# peripherals.net
KiCad netlist of a schematic drawn in Altium Designer
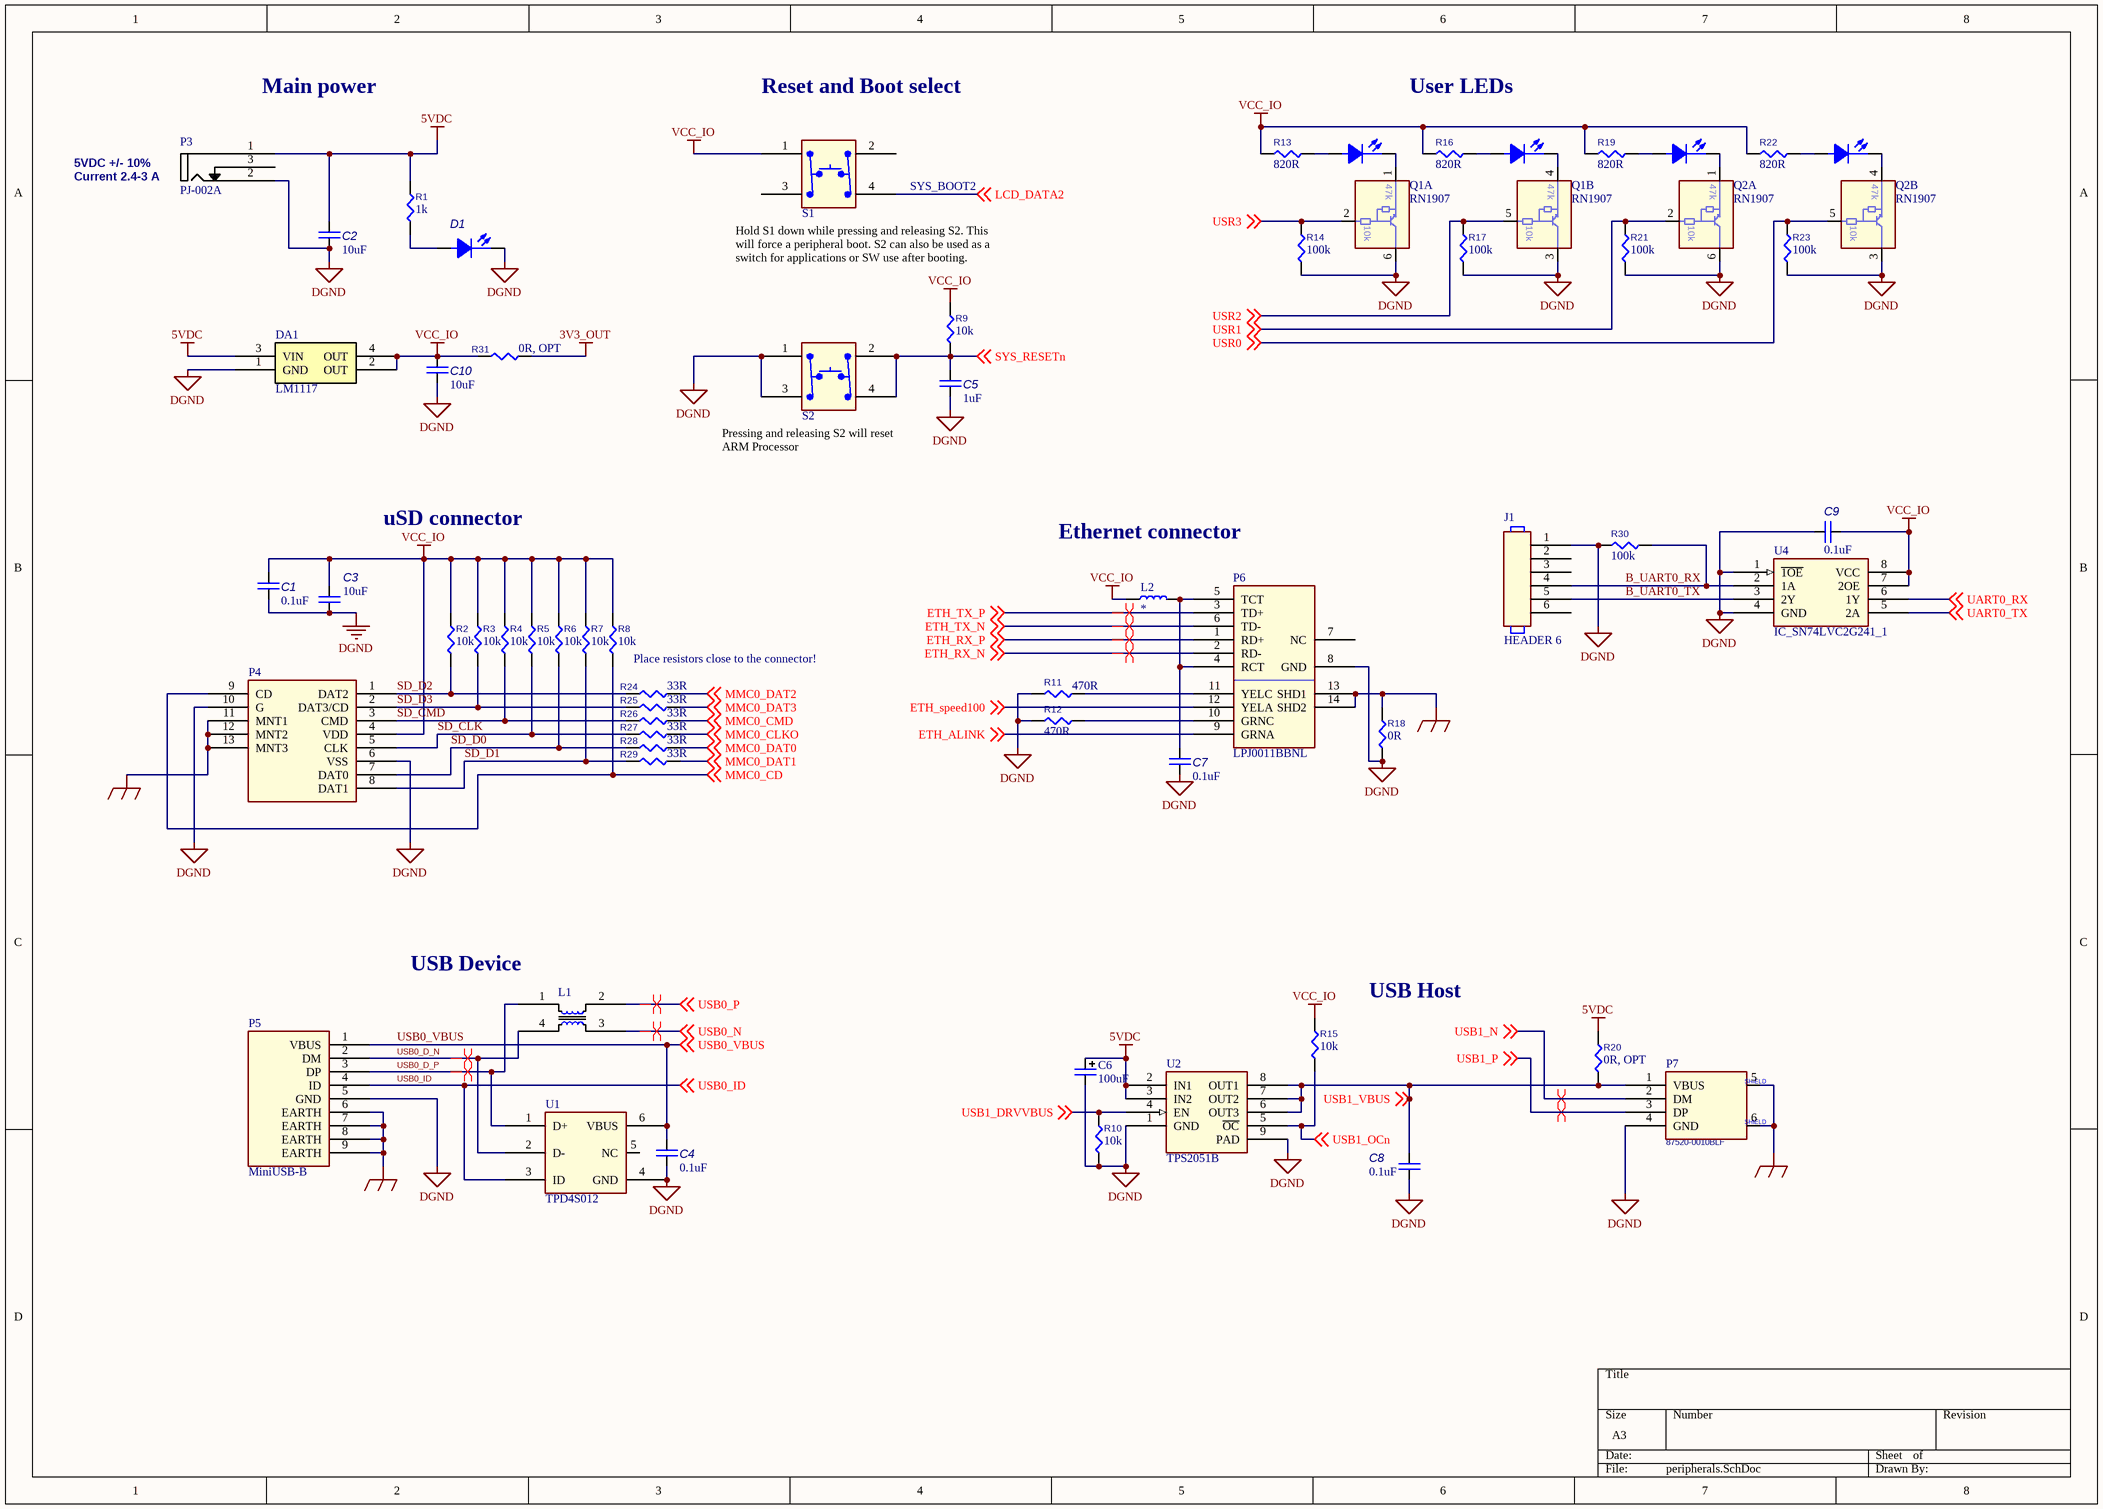
[diagram p0: peripherals.SchDoc]

(export (version "E")
  (design (tool "Eeschema 10.0.6"))
  (components
    (comp (ref "C1")
      (value "0.1uF")
      (footprint "CC1608-0603")
      (description "C0603")
      (libsource (lib "am335x-base") (part "C0603"))
    )
    (comp (ref "C2")
      (value "10uF")
      (footprint "CC2012-0805")
      (description "C0805")
      (libsource (lib "am335x-base") (part "C0805"))
    )
    (comp (ref "C3")
      (value "10uF")
      (footprint "CC2012-0805")
      (description "C0805")
      (libsource (lib "am335x-base") (part "C0805"))
    )
    (comp (ref "C4")
      (value "0.1uF")
      (footprint "CC1608-0603")
      (description "C0603")
      (libsource (lib "am335x-base") (part "C0603"))
    )
    (comp (ref "C5")
      (value "1uF")
      (footprint "CC1608-0603")
      (description "C0603")
      (libsource (lib "am335x-base") (part "C0603"))
    )
    (comp (ref "C6")
      (value "100uF")
      (footprint "Cap_C")
      (description "Tantalum Capacitor Case C")
      (fields (field (name "Comment") "Cap_C"))
      (libsource (lib "am335x-base") (part "Cap_C"))
    )
    (comp (ref "C7")
      (value "0.1uF")
      (footprint "CC1608-0603")
      (description "C0603")
      (libsource (lib "am335x-base") (part "C0603"))
    )
    (comp (ref "C8")
      (value "0.1uF")
      (footprint "CC1608-0603")
      (description "C0603")
      (libsource (lib "am335x-base") (part "C0603"))
    )
    (comp (ref "C9")
      (value "0.1uF")
      (footprint "CC1608-0603")
      (description "C0603")
      (libsource (lib "usomiq-base") (part "C0603"))
    )
    (comp (ref "C10")
      (value "10uF")
      (footprint "CC2012-0805")
      (description "C0805")
      (libsource (lib "am335x-base") (part "C0805"))
    )
    (comp (ref "D1")
      (value "LED0805")
      (footprint "LED0805")
      (description "LED 0805")
      (libsource (lib "am335x-base") (part "LED0805"))
    )
    (comp (ref "D2")
      (value "LED0805")
      (footprint "LED0805")
      (description "LED 0805")
      (libsource (lib "am335x-base") (part "LED0805"))
    )
    (comp (ref "D3")
      (value "LED0805")
      (footprint "LED0805")
      (description "LED 0805")
      (libsource (lib "am335x-base") (part "LED0805"))
    )
    (comp (ref "D4")
      (value "LED0805")
      (footprint "LED0805")
      (description "LED 0805")
      (libsource (lib "am335x-base") (part "LED0805"))
    )
    (comp (ref "D5")
      (value "LED0805")
      (footprint "LED0805")
      (description "LED 0805")
      (libsource (lib "am335x-base") (part "LED0805"))
    )
    (comp (ref "DA1")
      (value "LM1117")
      (footprint "SOT230P700X160-4N")
      (description "800mA Low-Dropout Linear Regulator")
      (fields (field (name "MANUFACTURER") "National"))
      (libsource (lib "usomiq-base") (part "LM1117"))
    )
    (comp (ref "J1")
      (value "HEADER 6")
      (footprint "DIP6")
      (description "CONN HEADER 6POS, VERTICAL,  .100 STR TIN")
      (fields (field (name "MFR") "FCI"))
      (libsource (lib "usomiq-base") (part "HEADER 6"))
    )
    (comp (ref "L1")
      (value "DLW21H")
      (footprint "DLW21H")
      (description "Low profile wire-wound common choke coil")
      (fields (field (name "MANUFACTURER") "Murata"))
      (libsource (lib "am335x-base") (part "DLW21H"))
    )
    (comp (ref "L2")
      (value "BLM18A-FB")
      (footprint "CHIP0603")
      (description "Chip EMIFILr Inductor Type")
      (fields (field (name "MANUFACTURER") "Murata") (field (name "MAN P/N") "*"))
      (libsource (lib "am335x-base") (part "BLM18A-FB"))
    )
    (comp (ref "P3")
      (value "PJ-002A")
      (footprint "PJ-002A")
      (description "DC POWER JACK")
      (fields (field (name "MANUFACTURER") "CIU Inc"))
      (libsource (lib "omap") (part "PJ-002A"))
    )
    (comp (ref "P4")
      (value "~")
      (footprint "TFC08WP01F-A-R1K-H")
      (description "Connector for microSD™ Card (Push-push Type)")
      (fields (field (name "MFR") "AUK Contractors Co, LTD"))
      (libsource (lib "usomiq-base") (part "TFC08WP01F-R1K-H-CN"))
    )
    (comp (ref "P5")
      (value "MiniUSB-B")
      (footprint "MINI-USB-B5 SMT")
      (description "Mini USB Type B CONNECTOR")
      (fields (field (name "MFR") "Hirose"))
      (libsource (lib "usomiq-base") (part "MiniUSB-B"))
    )
    (comp (ref "P6")
      (value "CONN_RJ45_MAG_WE_0")
      (footprint "TRJ0011ABNL")
      (description "RJ-45 10/100 W/Magnetics")
      (fields (field (name "MFR") "Link PP") (field (name "P/N") "LPJ0011BBNL"))
      (libsource (lib "am335x-base") (part "CONN_RJ45_MAG_WE_0"))
    )
    (comp (ref "P7")
      (value "CONN_54819-0578_2")
      (footprint "USB2.5-2H4C")
      (description "USB Type A Connectors")
      (fields (field (name "P/N") "87520-0010BLF") (field (name "MFR") "FCI"))
      (libsource (lib "am335x-base") (part "CONN_54819-0578_2"))
    )
    (comp (ref "Q1")
      (value "RN1907")
      (footprint "SOT363-6L")
      (description "Transistor Silicon NPN")
      (fields (field (name "MFR") "Panasonic"))
      (libsource (lib "am335x-base") (part "RN1907"))
    )
    (comp (ref "Q2")
      (value "RN1907")
      (footprint "SOT363-6L")
      (description "Transistor Silicon NPN")
      (fields (field (name "MFR") "Panasonic"))
      (libsource (lib "am335x-base") (part "RN1907"))
    )
    (comp (ref "R1")
      (value "1k")
      (footprint "RESC1608X55N")
      (description "R0603")
      (libsource (lib "am335x-base") (part "R0603"))
    )
    (comp (ref "R2")
      (value "10k")
      (footprint "RESC1608X55N")
      (description "R0603")
      (libsource (lib "am335x-base") (part "R0603"))
    )
    (comp (ref "R3")
      (value "10k")
      (footprint "RESC1608X55N")
      (description "R0603")
      (libsource (lib "am335x-base") (part "R0603"))
    )
    (comp (ref "R4")
      (value "10k")
      (footprint "RESC1608X55N")
      (description "R0603")
      (libsource (lib "am335x-base") (part "R0603"))
    )
    (comp (ref "R5")
      (value "10k")
      (footprint "RESC1608X55N")
      (description "R0603")
      (libsource (lib "am335x-base") (part "R0603"))
    )
    (comp (ref "R6")
      (value "10k")
      (footprint "RESC1608X55N")
      (description "R0603")
      (libsource (lib "am335x-base") (part "R0603"))
    )
    (comp (ref "R7")
      (value "10k")
      (footprint "RESC1608X55N")
      (description "R0603")
      (libsource (lib "am335x-base") (part "R0603"))
    )
    (comp (ref "R8")
      (value "10k")
      (footprint "RESC1608X55N")
      (description "R0603")
      (libsource (lib "am335x-base") (part "R0603"))
    )
    (comp (ref "R9")
      (value "10k")
      (footprint "RESC1608X55N")
      (description "R0603")
      (libsource (lib "am335x-base") (part "R0603"))
    )
    (comp (ref "R10")
      (value "10k")
      (footprint "RESC1608X55N")
      (description "R0603")
      (libsource (lib "am335x-base") (part "R0603"))
    )
    (comp (ref "R11")
      (value "470R")
      (footprint "RESC1608X55N")
      (description "R0603")
      (libsource (lib "am335x-base") (part "R0603"))
    )
    (comp (ref "R12")
      (value "470R")
      (footprint "RESC1608X55N")
      (description "R0603")
      (libsource (lib "am335x-base") (part "R0603"))
    )
    (comp (ref "R13")
      (value "820R")
      (footprint "RESC1608X55N")
      (description "R0603")
      (libsource (lib "am335x-base") (part "R0603"))
    )
    (comp (ref "R14")
      (value "100k")
      (footprint "RESC1608X55N")
      (description "R0603")
      (libsource (lib "am335x-base") (part "R0603"))
    )
    (comp (ref "R15")
      (value "10k")
      (footprint "RESC1608X55N")
      (description "R0603")
      (libsource (lib "am335x-base") (part "R0603"))
    )
    (comp (ref "R16")
      (value "820R")
      (footprint "RESC1608X55N")
      (description "R0603")
      (libsource (lib "am335x-base") (part "R0603"))
    )
    (comp (ref "R17")
      (value "100k")
      (footprint "RESC1608X55N")
      (description "R0603")
      (libsource (lib "am335x-base") (part "R0603"))
    )
    (comp (ref "R18")
      (value "0R")
      (footprint "RESC1608X55N")
      (description "R0603")
      (libsource (lib "am335x-base") (part "R0603"))
    )
    (comp (ref "R19")
      (value "820R")
      (footprint "RESC1608X55N")
      (description "R0603")
      (libsource (lib "am335x-base") (part "R0603"))
    )
    (comp (ref "R20")
      (value "0R, OPT")
      (footprint "RESC1608X55N")
      (description "R0603")
      (libsource (lib "am335x-base") (part "R0603"))
    )
    (comp (ref "R21")
      (value "100k")
      (footprint "RESC1608X55N")
      (description "R0603")
      (libsource (lib "am335x-base") (part "R0603"))
    )
    (comp (ref "R22")
      (value "820R")
      (footprint "RESC1608X55N")
      (description "R0603")
      (libsource (lib "am335x-base") (part "R0603"))
    )
    (comp (ref "R23")
      (value "100k")
      (footprint "RESC1608X55N")
      (description "R0603")
      (libsource (lib "am335x-base") (part "R0603"))
    )
    (comp (ref "R24")
      (value "33R")
      (footprint "RESC1608X55N")
      (description "R0603")
      (libsource (lib "usomiq-base") (part "R0603"))
    )
    (comp (ref "R25")
      (value "33R")
      (footprint "RESC1608X55N")
      (description "R0603")
      (libsource (lib "usomiq-base") (part "R0603"))
    )
    (comp (ref "R26")
      (value "33R")
      (footprint "RESC1608X55N")
      (description "R0603")
      (libsource (lib "usomiq-base") (part "R0603"))
    )
    (comp (ref "R27")
      (value "33R")
      (footprint "RESC1608X55N")
      (description "R0603")
      (libsource (lib "usomiq-base") (part "R0603"))
    )
    (comp (ref "R28")
      (value "33R")
      (footprint "RESC1608X55N")
      (description "R0603")
      (libsource (lib "usomiq-base") (part "R0603"))
    )
    (comp (ref "R29")
      (value "33R")
      (footprint "RESC1608X55N")
      (description "R0603")
      (libsource (lib "usomiq-base") (part "R0603"))
    )
    (comp (ref "R30")
      (value "100k")
      (footprint "RESC1608X55N")
      (description "R0603")
      (libsource (lib "am335x-base") (part "R0603"))
    )
    (comp (ref "R31")
      (value "0R, OPT")
      (footprint "RESC1608X55N")
      (description "R0603")
      (libsource (lib "usomiq-base") (part "R0603"))
    )
    (comp (ref "S1")
      (value "SW_KT11P2JM_2")
      (footprint "KMR231GLFS")
      (description "SMD button")
      (fields (field (name "MFR") "C&K Components"))
      (libsource (lib "usomiq-base") (part "SW_KT11P2JM_2"))
    )
    (comp (ref "S2")
      (value "SW_KT11P2JM_2")
      (footprint "KMR231GLFS")
      (description "SMD button")
      (fields (field (name "MFR") "C&K Components"))
      (libsource (lib "usomiq-base") (part "SW_KT11P2JM_2"))
    )
    (comp (ref "U1")
      (value "TPD4S012")
      (footprint "s-puson-n6")
      (description "4-Channel USB ESD Solution with Power Clamp")
      (fields (field (name "MFR") "TI"))
      (libsource (lib "usomiq-base") (part "TPD4S012"))
    )
    (comp (ref "U2")
      (value "TPS2051B")
      (footprint "R-PDSO-G8")
      (description "CURRENT-LIMITED, POWER-DISTRIBUTION SWITCHES")
      (fields (field (name "MFR") "TI"))
      (libsource (lib "usomiq-base") (part "TPS2051B"))
    )
    (comp (ref "U4")
      (value "IC_SN74LVC2G241_1")
      (footprint "SOP127P600-8N")
      (description "Dual Buffer/Driver With 3-State Outputs")
      (fields (field (name "MFR") "TI"))
      (libsource (lib "usomiq-base") (part "IC_SN74LVC2G241_1"))
    )
  )
  (nets
    (net (code "1") (name "/B_UART0_RX") (class "Default")
      (node (ref "J1") (pin "4") (pinfunction "4_4") (pintype "passive"))
      (node (ref "R30") (pin "1") (pinfunction "1_1") (pintype "passive"))
      (node (ref "U4") (pin "2") (pinfunction "1A_2") (pintype "passive"))
    )
    (net (code "2") (name "/B_UART0_TX") (class "Default")
      (node (ref "J1") (pin "5") (pinfunction "5_5") (pintype "passive"))
      (node (ref "U4") (pin "3") (pinfunction "2Y_3") (pintype "passive"))
    )
    (net (code "3") (name "/SD_CLK") (class "Default")
      (node (ref "P4") (pin "5") (pinfunction "CLK_5") (pintype "passive"))
      (node (ref "R27") (pin "1") (pinfunction "1_1") (pintype "passive"))
      (node (ref "R5") (pin "1") (pinfunction "1_1") (pintype "passive"))
    )
    (net (code "4") (name "/SD_CMD") (class "Default")
      (node (ref "P4") (pin "3") (pinfunction "CMD_3") (pintype "passive"))
      (node (ref "R26") (pin "1") (pinfunction "1_1") (pintype "passive"))
      (node (ref "R4") (pin "1") (pinfunction "1_1") (pintype "passive"))
    )
    (net (code "5") (name "/SD_D0") (class "Default")
      (node (ref "P4") (pin "7") (pinfunction "DAT0_7") (pintype "passive"))
      (node (ref "R28") (pin "1") (pinfunction "1_1") (pintype "passive"))
      (node (ref "R6") (pin "1") (pinfunction "1_1") (pintype "passive"))
    )
    (net (code "6") (name "/SD_D1") (class "Default")
      (node (ref "P4") (pin "8") (pinfunction "DAT1_8") (pintype "passive"))
      (node (ref "R29") (pin "1") (pinfunction "1_1") (pintype "passive"))
      (node (ref "R7") (pin "1") (pinfunction "1_1") (pintype "passive"))
    )
    (net (code "7") (name "/SD_D2") (class "Default")
      (node (ref "P4") (pin "1") (pinfunction "DAT2_1") (pintype "passive"))
      (node (ref "R2") (pin "1") (pinfunction "1_1") (pintype "passive"))
      (node (ref "R24") (pin "1") (pinfunction "1_1") (pintype "passive"))
    )
    (net (code "8") (name "/SD_D3") (class "Default")
      (node (ref "P4") (pin "2") (pinfunction "DAT3/CD_2") (pintype "passive"))
      (node (ref "R25") (pin "1") (pinfunction "1_1") (pintype "passive"))
      (node (ref "R3") (pin "1") (pinfunction "1_1") (pintype "passive"))
    )
    (net (code "9") (name "/USB0_D_N") (class "Default")
      (node (ref "L1") (pin "4") (pinfunction "4_4") (pintype "passive"))
      (node (ref "P5") (pin "2") (pinfunction "DM_2") (pintype "passive"))
      (node (ref "U1") (pin "2") (pinfunction "D-_2") (pintype "passive"))
    )
    (net (code "10") (name "/USB0_D_P") (class "Default")
      (node (ref "L1") (pin "1") (pinfunction "1_1") (pintype "passive"))
      (node (ref "P5") (pin "3") (pinfunction "DP_3") (pintype "passive"))
      (node (ref "U1") (pin "1") (pinfunction "D+_1") (pintype "passive"))
    )
    (net (code "11") (name "3V3_OUT") (class "Default")
      (node (ref "R31") (pin "2") (pinfunction "2_2") (pintype "passive"))
    )
    (net (code "12") (name "5VDC") (class "Default")
      (node (ref "C2") (pin "2") (pinfunction "2_2") (pintype "passive"))
      (node (ref "C6") (pin "1") (pinfunction "1_1") (pintype "passive"))
      (node (ref "DA1") (pin "3") (pinfunction "VIN_3") (pintype "power_in"))
      (node (ref "P3") (pin "1") (pinfunction "GND_1") (pintype "passive"))
      (node (ref "R1") (pin "2") (pinfunction "2_2") (pintype "passive"))
      (node (ref "R20") (pin "2") (pinfunction "2_2") (pintype "passive"))
      (node (ref "U2") (pin "2") (pinfunction "IN1_2") (pintype "power_in"))
      (node (ref "U2") (pin "3") (pinfunction "IN2_3") (pintype "power_in"))
    )
    (net (code "13") (name "DGND") (class "Default")
      (node (ref "C1") (pin "2") (pinfunction "2_2") (pintype "passive"))
      (node (ref "C10") (pin "1") (pinfunction "1_1") (pintype "passive"))
      (node (ref "C2") (pin "1") (pinfunction "1_1") (pintype "passive"))
      (node (ref "C3") (pin "1") (pinfunction "1_1") (pintype "passive"))
      (node (ref "C4") (pin "2") (pinfunction "2_2") (pintype "passive"))
      (node (ref "C5") (pin "2") (pinfunction "2_2") (pintype "passive"))
      (node (ref "C6") (pin "2") (pinfunction "2_2") (pintype "passive"))
      (node (ref "C7") (pin "2") (pinfunction "2_2") (pintype "passive"))
      (node (ref "C8") (pin "1") (pinfunction "1_1") (pintype "passive"))
      (node (ref "C9") (pin "1") (pinfunction "1_1") (pintype "passive"))
      (node (ref "D1") (pin "2") (pinfunction "C_2") (pintype "passive"))
      (node (ref "DA1") (pin "1") (pinfunction "GND_1") (pintype "power_in"))
      (node (ref "J1") (pin "1") (pinfunction "1_1") (pintype "passive"))
      (node (ref "P3") (pin "2") (pinfunction "RIGHT_2") (pintype "passive"))
      (node (ref "P4") (pin "10") (pinfunction "G_10") (pintype "passive"))
      (node (ref "P4") (pin "6") (pinfunction "VSS_6") (pintype "power_in"))
      (node (ref "P5") (pin "5") (pinfunction "GND_5") (pintype "power_in"))
      (node (ref "P6") (pin "8") (pinfunction "GND_8") (pintype "passive"))
      (node (ref "P7") (pin "4") (pinfunction "GND_4") (pintype "passive"))
      (node (ref "Q1") (pin "3") (pinfunction "3_3") (pintype "passive"))
      (node (ref "Q1") (pin "6") (pinfunction "3_6") (pintype "passive"))
      (node (ref "Q2") (pin "3") (pinfunction "3_3") (pintype "passive"))
      (node (ref "Q2") (pin "6") (pinfunction "3_6") (pintype "passive"))
      (node (ref "R10") (pin "1") (pinfunction "1_1") (pintype "passive"))
      (node (ref "R11") (pin "1") (pinfunction "1_1") (pintype "passive"))
      (node (ref "R12") (pin "1") (pinfunction "1_1") (pintype "passive"))
      (node (ref "R14") (pin "1") (pinfunction "1_1") (pintype "passive"))
      (node (ref "R17") (pin "1") (pinfunction "1_1") (pintype "passive"))
      (node (ref "R18") (pin "1") (pinfunction "1_1") (pintype "passive"))
      (node (ref "R21") (pin "1") (pinfunction "1_1") (pintype "passive"))
      (node (ref "R23") (pin "1") (pinfunction "1_1") (pintype "passive"))
      (node (ref "R30") (pin "2") (pinfunction "2_2") (pintype "passive"))
      (node (ref "S2") (pin "1") (pinfunction "A1_1") (pintype "passive"))
      (node (ref "S2") (pin "3") (pinfunction "A2_3") (pintype "passive"))
      (node (ref "U1") (pin "4") (pinfunction "GND_4") (pintype "power_in"))
      (node (ref "U2") (pin "1") (pinfunction "GND_1") (pintype "power_in"))
      (node (ref "U2") (pin "9") (pinfunction "PAD_9") (pintype "passive"))
      (node (ref "U4") (pin "1") (pinfunction "~{1OE}_1") (pintype "input"))
      (node (ref "U4") (pin "4") (pinfunction "GND_4") (pintype "power_in"))
    )
    (net (code "14") (name "EARTH") (class "Default")
      (node (ref "P4") (pin "11") (pinfunction "MNT1_11") (pintype "passive"))
      (node (ref "P4") (pin "12") (pinfunction "MNT2_12") (pintype "passive"))
      (node (ref "P4") (pin "13") (pinfunction "MNT3_13") (pintype "passive"))
      (node (ref "P5") (pin "6") (pinfunction "EARTH_6") (pintype "passive"))
      (node (ref "P5") (pin "7") (pinfunction "EARTH_7") (pintype "passive"))
      (node (ref "P5") (pin "8") (pinfunction "EARTH_8") (pintype "passive"))
      (node (ref "P5") (pin "9") (pinfunction "EARTH_9") (pintype "passive"))
      (node (ref "P6") (pin "13") (pinfunction "SHD1_13") (pintype "passive"))
      (node (ref "P6") (pin "14") (pinfunction "SHD2_14") (pintype "passive"))
      (node (ref "P7") (pin "5") (pinfunction "SHELD1_5") (pintype "passive"))
      (node (ref "P7") (pin "6") (pinfunction "PAD4_6") (pintype "passive"))
      (node (ref "R18") (pin "2") (pinfunction "2_2") (pintype "passive"))
    )
    (net (code "15") (name "ETH_ALINK") (class "Default")
      (node (ref "P6") (pin "9") (pinfunction "GRNA_9") (pintype "passive"))
    )
    (net (code "16") (name "ETH_RX_N") (class "Default")
      (node (ref "P6") (pin "2") (pinfunction "RD-_2") (pintype "passive"))
    )
    (net (code "17") (name "ETH_RX_P") (class "Default")
      (node (ref "P6") (pin "1") (pinfunction "RD+_1") (pintype "passive"))
    )
    (net (code "18") (name "ETH_TX_N") (class "Default")
      (node (ref "P6") (pin "6") (pinfunction "TD-_6") (pintype "passive"))
    )
    (net (code "19") (name "ETH_TX_P") (class "Default")
      (node (ref "P6") (pin "3") (pinfunction "TD+_3") (pintype "passive"))
    )
    (net (code "20") (name "ETH_speed100") (class "Default")
      (node (ref "P6") (pin "12") (pinfunction "YELA_12") (pintype "passive"))
    )
    (net (code "21") (name "LCD_DATA2") (class "Default")
      (node (ref "S1") (pin "4") (pinfunction "B2_4") (pintype "passive"))
    )
    (net (code "22") (name "MMC0_CD") (class "Default")
      (node (ref "P4") (pin "9") (pinfunction "CD_9") (pintype "passive"))
      (node (ref "R8") (pin "1") (pinfunction "1_1") (pintype "passive"))
    )
    (net (code "23") (name "MMC0_CLKO") (class "Default")
      (node (ref "R27") (pin "2") (pinfunction "2_2") (pintype "passive"))
    )
    (net (code "24") (name "MMC0_CMD") (class "Default")
      (node (ref "R26") (pin "2") (pinfunction "2_2") (pintype "passive"))
    )
    (net (code "25") (name "MMC0_DAT0") (class "Default")
      (node (ref "R28") (pin "2") (pinfunction "2_2") (pintype "passive"))
    )
    (net (code "26") (name "MMC0_DAT1") (class "Default")
      (node (ref "R29") (pin "2") (pinfunction "2_2") (pintype "passive"))
    )
    (net (code "27") (name "MMC0_DAT2") (class "Default")
      (node (ref "R24") (pin "2") (pinfunction "2_2") (pintype "passive"))
    )
    (net (code "28") (name "MMC0_DAT3") (class "Default")
      (node (ref "R25") (pin "2") (pinfunction "2_2") (pintype "passive"))
    )
    (net (code "29") (name "Net-(D1-A)") (class "Default")
      (node (ref "D1") (pin "1") (pinfunction "A_1") (pintype "passive"))
      (node (ref "R1") (pin "1") (pinfunction "1_1") (pintype "passive"))
    )
    (net (code "30") (name "Net-(D2-A)") (class "Default")
      (node (ref "D2") (pin "1") (pinfunction "A_1") (pintype "passive"))
      (node (ref "R13") (pin "1") (pinfunction "1_1") (pintype "passive"))
    )
    (net (code "31") (name "Net-(D2-C)") (class "Default")
      (node (ref "D2") (pin "2") (pinfunction "C_2") (pintype "passive"))
      (node (ref "Q1") (pin "1") (pinfunction "4_1") (pintype "passive"))
    )
    (net (code "32") (name "Net-(D3-A)") (class "Default")
      (node (ref "D3") (pin "1") (pinfunction "A_1") (pintype "passive"))
      (node (ref "R16") (pin "1") (pinfunction "1_1") (pintype "passive"))
    )
    (net (code "33") (name "Net-(D3-C)") (class "Default")
      (node (ref "D3") (pin "2") (pinfunction "C_2") (pintype "passive"))
      (node (ref "Q1") (pin "4") (pinfunction "4_4") (pintype "passive"))
    )
    (net (code "34") (name "Net-(D4-A)") (class "Default")
      (node (ref "D4") (pin "1") (pinfunction "A_1") (pintype "passive"))
      (node (ref "R19") (pin "1") (pinfunction "1_1") (pintype "passive"))
    )
    (net (code "35") (name "Net-(D4-C)") (class "Default")
      (node (ref "D4") (pin "2") (pinfunction "C_2") (pintype "passive"))
      (node (ref "Q2") (pin "1") (pinfunction "4_1") (pintype "passive"))
    )
    (net (code "36") (name "Net-(D5-A)") (class "Default")
      (node (ref "D5") (pin "1") (pinfunction "A_1") (pintype "passive"))
      (node (ref "R22") (pin "1") (pinfunction "1_1") (pintype "passive"))
    )
    (net (code "37") (name "Net-(D5-C)") (class "Default")
      (node (ref "D5") (pin "2") (pinfunction "C_2") (pintype "passive"))
      (node (ref "Q2") (pin "4") (pinfunction "4_4") (pintype "passive"))
    )
    (net (code "38") (name "Net-(P6-GRNC)") (class "Default")
      (node (ref "P6") (pin "10") (pinfunction "GRNC_10") (pintype "passive"))
      (node (ref "R12") (pin "2") (pinfunction "2_2") (pintype "passive"))
    )
    (net (code "39") (name "Net-(P6-RCT)") (class "Default")
      (node (ref "C7") (pin "1") (pinfunction "1_1") (pintype "passive"))
      (node (ref "L2") (pin "2") (pinfunction "2_2") (pintype "passive"))
      (node (ref "P6") (pin "4") (pinfunction "RCT_4") (pintype "passive"))
      (node (ref "P6") (pin "5") (pinfunction "TCT_5") (pintype "passive"))
    )
    (net (code "40") (name "Net-(P6-YELC)") (class "Default")
      (node (ref "P6") (pin "11") (pinfunction "YELC_11") (pintype "passive"))
      (node (ref "R11") (pin "2") (pinfunction "2_2") (pintype "passive"))
    )
    (net (code "41") (name "SYS_RESETn") (class "Default")
      (node (ref "C5") (pin "1") (pinfunction "1_1") (pintype "passive"))
      (node (ref "R9") (pin "1") (pinfunction "1_1") (pintype "passive"))
      (node (ref "S2") (pin "2") (pinfunction "B1_2") (pintype "passive"))
      (node (ref "S2") (pin "4") (pinfunction "B2_4") (pintype "passive"))
    )
    (net (code "42") (name "UART0_RX") (class "Default")
      (node (ref "U4") (pin "6") (pinfunction "1Y_6") (pintype "passive"))
    )
    (net (code "43") (name "UART0_TX") (class "Default")
      (node (ref "U4") (pin "5") (pinfunction "2A_5") (pintype "passive"))
    )
    (net (code "44") (name "USB0_ID") (class "Default")
      (node (ref "P5") (pin "4") (pinfunction "ID_4") (pintype "passive"))
      (node (ref "U1") (pin "3") (pinfunction "ID_3") (pintype "passive"))
    )
    (net (code "45") (name "USB0_N") (class "Default")
      (node (ref "L1") (pin "3") (pinfunction "3_3") (pintype "passive"))
    )
    (net (code "46") (name "USB0_P") (class "Default")
      (node (ref "L1") (pin "2") (pinfunction "2_2") (pintype "passive"))
    )
    (net (code "47") (name "USB0_VBUS") (class "Default")
      (node (ref "C4") (pin "1") (pinfunction "1_1") (pintype "passive"))
      (node (ref "P5") (pin "1") (pinfunction "VBUS_1") (pintype "power_in"))
      (node (ref "U1") (pin "6") (pinfunction "VBUS_6") (pintype "power_in"))
    )
    (net (code "48") (name "USB1_DRVVBUS") (class "Default")
      (node (ref "R10") (pin "2") (pinfunction "2_2") (pintype "passive"))
      (node (ref "U2") (pin "4") (pinfunction "EN_4") (pintype "input"))
    )
    (net (code "49") (name "USB1_N") (class "Default")
      (node (ref "P7") (pin "2") (pinfunction "DM_2") (pintype "passive"))
    )
    (net (code "50") (name "USB1_OCn") (class "Default")
      (node (ref "R15") (pin "1") (pinfunction "1_1") (pintype "passive"))
      (node (ref "U2") (pin "5") (pinfunction "~{OC}_5") (pintype "passive"))
    )
    (net (code "51") (name "USB1_P") (class "Default")
      (node (ref "P7") (pin "3") (pinfunction "DP_3") (pintype "passive"))
    )
    (net (code "52") (name "USB1_VBUS") (class "Default")
      (node (ref "C8") (pin "2") (pinfunction "2_2") (pintype "passive"))
      (node (ref "P7") (pin "1") (pinfunction "VBUS_1") (pintype "passive"))
      (node (ref "R20") (pin "1") (pinfunction "1_1") (pintype "passive"))
      (node (ref "U2") (pin "6") (pinfunction "OUT3_6") (pintype "power_in"))
      (node (ref "U2") (pin "7") (pinfunction "OUT2_7") (pintype "power_in"))
      (node (ref "U2") (pin "8") (pinfunction "OUT1_8") (pintype "power_in"))
    )
    (net (code "53") (name "USR0") (class "Default")
      (node (ref "Q2") (pin "5") (pinfunction "5_5") (pintype "passive"))
      (node (ref "R23") (pin "2") (pinfunction "2_2") (pintype "passive"))
    )
    (net (code "54") (name "USR1") (class "Default")
      (node (ref "Q2") (pin "2") (pinfunction "5_2") (pintype "passive"))
      (node (ref "R21") (pin "2") (pinfunction "2_2") (pintype "passive"))
    )
    (net (code "55") (name "USR2") (class "Default")
      (node (ref "Q1") (pin "5") (pinfunction "5_5") (pintype "passive"))
      (node (ref "R17") (pin "2") (pinfunction "2_2") (pintype "passive"))
    )
    (net (code "56") (name "USR3") (class "Default")
      (node (ref "Q1") (pin "2") (pinfunction "5_2") (pintype "passive"))
      (node (ref "R14") (pin "2") (pinfunction "2_2") (pintype "passive"))
    )
    (net (code "57") (name "VCC_IO") (class "Default")
      (node (ref "C1") (pin "1") (pinfunction "1_1") (pintype "passive"))
      (node (ref "C10") (pin "2") (pinfunction "2_2") (pintype "passive"))
      (node (ref "C3") (pin "2") (pinfunction "2_2") (pintype "passive"))
      (node (ref "C9") (pin "2") (pinfunction "2_2") (pintype "passive"))
      (node (ref "DA1") (pin "2") (pinfunction "OUT_2") (pintype "power_in"))
      (node (ref "DA1") (pin "4") (pinfunction "OUT_4") (pintype "power_in"))
      (node (ref "L2") (pin "1") (pinfunction "1_1") (pintype "passive"))
      (node (ref "P4") (pin "4") (pinfunction "VDD_4") (pintype "power_in"))
      (node (ref "R13") (pin "2") (pinfunction "2_2") (pintype "passive"))
      (node (ref "R15") (pin "2") (pinfunction "2_2") (pintype "passive"))
      (node (ref "R16") (pin "2") (pinfunction "2_2") (pintype "passive"))
      (node (ref "R19") (pin "2") (pinfunction "2_2") (pintype "passive"))
      (node (ref "R2") (pin "2") (pinfunction "2_2") (pintype "passive"))
      (node (ref "R22") (pin "2") (pinfunction "2_2") (pintype "passive"))
      (node (ref "R3") (pin "2") (pinfunction "2_2") (pintype "passive"))
      (node (ref "R31") (pin "1") (pinfunction "1_1") (pintype "passive"))
      (node (ref "R4") (pin "2") (pinfunction "2_2") (pintype "passive"))
      (node (ref "R5") (pin "2") (pinfunction "2_2") (pintype "passive"))
      (node (ref "R6") (pin "2") (pinfunction "2_2") (pintype "passive"))
      (node (ref "R7") (pin "2") (pinfunction "2_2") (pintype "passive"))
      (node (ref "R8") (pin "2") (pinfunction "2_2") (pintype "passive"))
      (node (ref "R9") (pin "2") (pinfunction "2_2") (pintype "passive"))
      (node (ref "S1") (pin "1") (pinfunction "A1_1") (pintype "passive"))
      (node (ref "U4") (pin "7") (pinfunction "2OE_7") (pintype "passive"))
      (node (ref "U4") (pin "8") (pinfunction "VCC_8") (pintype "power_in"))
    )
    (net (code "58") (name "unconnected-(J1-Pad2)") (class "Default")
      (node (ref "J1") (pin "2") (pinfunction "2_2") (pintype "passive"))
    )
    (net (code "59") (name "unconnected-(J1-Pad3)") (class "Default")
      (node (ref "J1") (pin "3") (pinfunction "3_3") (pintype "passive"))
    )
    (net (code "60") (name "unconnected-(J1-Pad6)") (class "Default")
      (node (ref "J1") (pin "6") (pinfunction "6_6") (pintype "passive"))
    )
    (net (code "61") (name "unconnected-(P3-LEFT-Pad3)") (class "Default")
      (node (ref "P3") (pin "3") (pinfunction "LEFT_3") (pintype "passive"))
    )
    (net (code "62") (name "unconnected-(P6-NC-Pad7)") (class "Default")
      (node (ref "P6") (pin "7") (pinfunction "NC_7") (pintype "passive"))
    )
    (net (code "63") (name "unconnected-(S1-A2-Pad3)") (class "Default")
      (node (ref "S1") (pin "3") (pinfunction "A2_3") (pintype "passive"))
    )
    (net (code "64") (name "unconnected-(S1-B1-Pad2)") (class "Default")
      (node (ref "S1") (pin "2") (pinfunction "B1_2") (pintype "passive"))
    )
    (net (code "65") (name "unconnected-(U1-NC-Pad5)") (class "Default")
      (node (ref "U1") (pin "5") (pinfunction "NC_5") (pintype "passive"))
    )
  )
)
